# CAN_Line.net
KiCad netlist of a schematic drawn in EAGLE
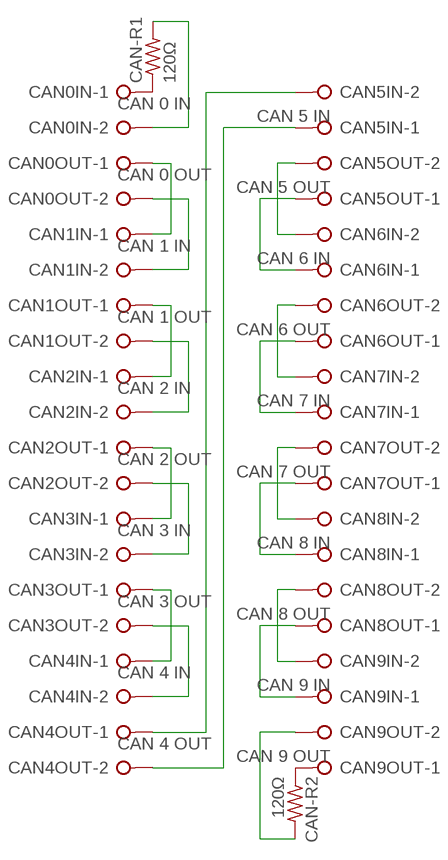
[diagram p0: schematic, sheet 1]

(export (version "E")
  (design (tool "Eeschema 10.0.6"))
  (components
    (comp (ref "CAN-R1")
      (value "120Ω")
      (footprint "eagle-import:0207_10")
      (libsource (lib "eagle-import") (part "R-US_0207/10"))
    )
    (comp (ref "CAN-R2")
      (value "120Ω")
      (footprint "eagle-import:0207_10")
      (libsource (lib "eagle-import") (part "R-US_0207/10"))
    )
    (comp (ref "CAN0IN")
      (value "CAN 0 IN")
      (footprint "eagle-import:W237-132")
      (libsource (lib "eagle-import") (part "W237-02P"))
    )
    (comp (ref "CAN0OUT")
      (value "CAN 0 OUT")
      (footprint "eagle-import:W237-132")
      (libsource (lib "eagle-import") (part "W237-02P"))
    )
    (comp (ref "CAN1IN")
      (value "CAN 1 IN")
      (footprint "eagle-import:W237-132")
      (libsource (lib "eagle-import") (part "W237-02P"))
    )
    (comp (ref "CAN1OUT")
      (value "CAN 1 OUT")
      (footprint "eagle-import:W237-132")
      (libsource (lib "eagle-import") (part "W237-02P"))
    )
    (comp (ref "CAN2IN")
      (value "CAN 2 IN")
      (footprint "eagle-import:W237-132")
      (libsource (lib "eagle-import") (part "W237-02P"))
    )
    (comp (ref "CAN2OUT")
      (value "CAN 2 OUT")
      (footprint "eagle-import:W237-132")
      (libsource (lib "eagle-import") (part "W237-02P"))
    )
    (comp (ref "CAN3IN")
      (value "CAN 3 IN")
      (footprint "eagle-import:W237-132")
      (libsource (lib "eagle-import") (part "W237-02P"))
    )
    (comp (ref "CAN3OUT")
      (value "CAN 3 OUT")
      (footprint "eagle-import:W237-132")
      (libsource (lib "eagle-import") (part "W237-02P"))
    )
    (comp (ref "CAN4IN")
      (value "CAN 4 IN")
      (footprint "eagle-import:W237-132")
      (libsource (lib "eagle-import") (part "W237-02P"))
    )
    (comp (ref "CAN4OUT")
      (value "CAN 4 OUT")
      (footprint "eagle-import:W237-132")
      (libsource (lib "eagle-import") (part "W237-02P"))
    )
    (comp (ref "CAN5IN")
      (value "CAN 5 IN")
      (footprint "eagle-import:W237-132")
      (libsource (lib "eagle-import") (part "W237-02P"))
    )
    (comp (ref "CAN5OUT")
      (value "CAN 5 OUT")
      (footprint "eagle-import:W237-132")
      (libsource (lib "eagle-import") (part "W237-02P"))
    )
    (comp (ref "CAN6IN")
      (value "CAN 6 IN")
      (footprint "eagle-import:W237-132")
      (libsource (lib "eagle-import") (part "W237-02P"))
    )
    (comp (ref "CAN6OUT")
      (value "CAN 6 OUT")
      (footprint "eagle-import:W237-132")
      (libsource (lib "eagle-import") (part "W237-02P"))
    )
    (comp (ref "CAN7IN")
      (value "CAN 7 IN")
      (footprint "eagle-import:W237-132")
      (libsource (lib "eagle-import") (part "W237-02P"))
    )
    (comp (ref "CAN7OUT")
      (value "CAN 7 OUT")
      (footprint "eagle-import:W237-132")
      (libsource (lib "eagle-import") (part "W237-02P"))
    )
    (comp (ref "CAN8IN")
      (value "CAN 8 IN")
      (footprint "eagle-import:W237-132")
      (libsource (lib "eagle-import") (part "W237-02P"))
    )
    (comp (ref "CAN8OUT")
      (value "CAN 8 OUT")
      (footprint "eagle-import:W237-132")
      (libsource (lib "eagle-import") (part "W237-02P"))
    )
    (comp (ref "CAN9IN")
      (value "CAN 9 IN")
      (footprint "eagle-import:W237-132")
      (libsource (lib "eagle-import") (part "W237-02P"))
    )
    (comp (ref "CAN9OUT")
      (value "CAN 9 OUT")
      (footprint "eagle-import:W237-132")
      (libsource (lib "eagle-import") (part "W237-02P"))
    )
  )
  (nets
    (net (code "1") (name "Net-(CAN0INA-KL)") (class "Default")
      (node (ref "CAN-R1") (pin "1") (pinfunction "1_1") (pintype "passive"))
      (node (ref "CAN0IN") (pin "1") (pinfunction "KL_1") (pintype "passive"))
    )
    (net (code "2") (name "Net-(CAN0INB-KL)") (class "Default")
      (node (ref "CAN-R1") (pin "2") (pinfunction "2_2") (pintype "passive"))
      (node (ref "CAN0IN") (pin "2") (pinfunction "KL_2") (pintype "passive"))
    )
    (net (code "3") (name "Net-(CAN0OUTA-KL)") (class "Default")
      (node (ref "CAN0OUT") (pin "1") (pinfunction "KL_1") (pintype "passive"))
      (node (ref "CAN1IN") (pin "1") (pinfunction "KL_1") (pintype "passive"))
    )
    (net (code "4") (name "Net-(CAN0OUTB-KL)") (class "Default")
      (node (ref "CAN0OUT") (pin "2") (pinfunction "KL_2") (pintype "passive"))
      (node (ref "CAN1IN") (pin "2") (pinfunction "KL_2") (pintype "passive"))
    )
    (net (code "5") (name "Net-(CAN1OUTA-KL)") (class "Default")
      (node (ref "CAN1OUT") (pin "1") (pinfunction "KL_1") (pintype "passive"))
      (node (ref "CAN2IN") (pin "1") (pinfunction "KL_1") (pintype "passive"))
    )
    (net (code "6") (name "Net-(CAN1OUTB-KL)") (class "Default")
      (node (ref "CAN1OUT") (pin "2") (pinfunction "KL_2") (pintype "passive"))
      (node (ref "CAN2IN") (pin "2") (pinfunction "KL_2") (pintype "passive"))
    )
    (net (code "7") (name "Net-(CAN2OUTA-KL)") (class "Default")
      (node (ref "CAN2OUT") (pin "1") (pinfunction "KL_1") (pintype "passive"))
      (node (ref "CAN3IN") (pin "1") (pinfunction "KL_1") (pintype "passive"))
    )
    (net (code "8") (name "Net-(CAN2OUTB-KL)") (class "Default")
      (node (ref "CAN2OUT") (pin "2") (pinfunction "KL_2") (pintype "passive"))
      (node (ref "CAN3IN") (pin "2") (pinfunction "KL_2") (pintype "passive"))
    )
    (net (code "9") (name "Net-(CAN3OUTA-KL)") (class "Default")
      (node (ref "CAN3OUT") (pin "1") (pinfunction "KL_1") (pintype "passive"))
      (node (ref "CAN4IN") (pin "1") (pinfunction "KL_1") (pintype "passive"))
    )
    (net (code "10") (name "Net-(CAN3OUTB-KL)") (class "Default")
      (node (ref "CAN3OUT") (pin "2") (pinfunction "KL_2") (pintype "passive"))
      (node (ref "CAN4IN") (pin "2") (pinfunction "KL_2") (pintype "passive"))
    )
    (net (code "11") (name "Net-(CAN4OUTA-KL)") (class "Default")
      (node (ref "CAN4OUT") (pin "1") (pinfunction "KL_1") (pintype "passive"))
      (node (ref "CAN5IN") (pin "2") (pinfunction "KL_2") (pintype "passive"))
    )
    (net (code "12") (name "Net-(CAN4OUTB-KL)") (class "Default")
      (node (ref "CAN4OUT") (pin "2") (pinfunction "KL_2") (pintype "passive"))
      (node (ref "CAN5IN") (pin "1") (pinfunction "KL_1") (pintype "passive"))
    )
    (net (code "13") (name "Net-(CAN5OUTA-KL)") (class "Default")
      (node (ref "CAN5OUT") (pin "1") (pinfunction "KL_1") (pintype "passive"))
      (node (ref "CAN6IN") (pin "1") (pinfunction "KL_1") (pintype "passive"))
    )
    (net (code "14") (name "Net-(CAN5OUTB-KL)") (class "Default")
      (node (ref "CAN5OUT") (pin "2") (pinfunction "KL_2") (pintype "passive"))
      (node (ref "CAN6IN") (pin "2") (pinfunction "KL_2") (pintype "passive"))
    )
    (net (code "15") (name "Net-(CAN6OUTA-KL)") (class "Default")
      (node (ref "CAN6OUT") (pin "1") (pinfunction "KL_1") (pintype "passive"))
      (node (ref "CAN7IN") (pin "1") (pinfunction "KL_1") (pintype "passive"))
    )
    (net (code "16") (name "Net-(CAN6OUTB-KL)") (class "Default")
      (node (ref "CAN6OUT") (pin "2") (pinfunction "KL_2") (pintype "passive"))
      (node (ref "CAN7IN") (pin "2") (pinfunction "KL_2") (pintype "passive"))
    )
    (net (code "17") (name "Net-(CAN7OUTA-KL)") (class "Default")
      (node (ref "CAN7OUT") (pin "1") (pinfunction "KL_1") (pintype "passive"))
      (node (ref "CAN8IN") (pin "1") (pinfunction "KL_1") (pintype "passive"))
    )
    (net (code "18") (name "Net-(CAN7OUTB-KL)") (class "Default")
      (node (ref "CAN7OUT") (pin "2") (pinfunction "KL_2") (pintype "passive"))
      (node (ref "CAN8IN") (pin "2") (pinfunction "KL_2") (pintype "passive"))
    )
    (net (code "19") (name "Net-(CAN8OUTA-KL)") (class "Default")
      (node (ref "CAN8OUT") (pin "1") (pinfunction "KL_1") (pintype "passive"))
      (node (ref "CAN9IN") (pin "1") (pinfunction "KL_1") (pintype "passive"))
    )
    (net (code "20") (name "Net-(CAN8OUTB-KL)") (class "Default")
      (node (ref "CAN8OUT") (pin "2") (pinfunction "KL_2") (pintype "passive"))
      (node (ref "CAN9IN") (pin "2") (pinfunction "KL_2") (pintype "passive"))
    )
    (net (code "21") (name "Net-(CAN9OUTA-KL)") (class "Default")
      (node (ref "CAN-R2") (pin "1") (pinfunction "1_1") (pintype "passive"))
      (node (ref "CAN9OUT") (pin "1") (pinfunction "KL_1") (pintype "passive"))
    )
    (net (code "22") (name "Net-(CAN9OUTB-KL)") (class "Default")
      (node (ref "CAN-R2") (pin "2") (pinfunction "2_2") (pintype "passive"))
      (node (ref "CAN9OUT") (pin "2") (pinfunction "KL_2") (pintype "passive"))
    )
  )
)
